# calefactor.net
KiCad netlist of a schematic drawn in EAGLE
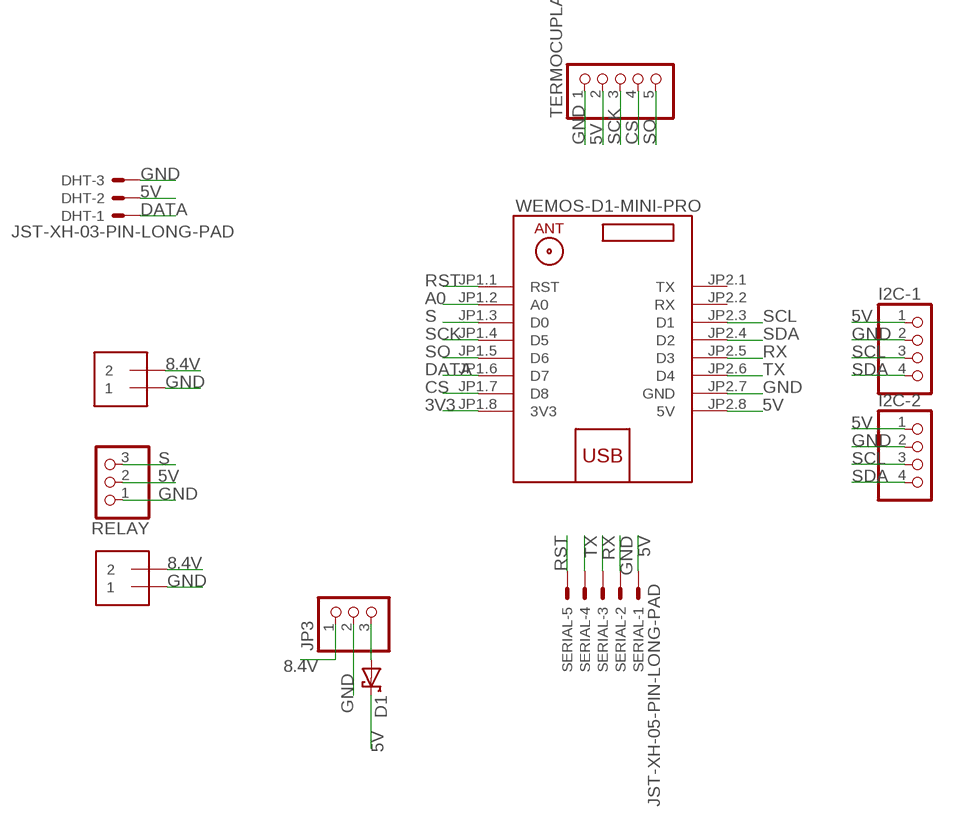
[diagram p0: schematic, sheet 1]

(export (version "E")
  (design (tool "Eeschema 10.0.6"))
  (components
    (comp (ref "D1")
      (value "SCHOTTKY-DIODEDO41-7")
      (footprint "eagle-import:DO41-7")
      (libsource (lib "eagle-import") (part "SCHOTTKY-DIODEDO41-7"))
    )
    (comp (ref "DHT")
      (value "JST-XH-03-PIN-LONG-PAD")
      (footprint "eagle-import:JST-XH-03-PACKAGE-LONG-PAD")
      (libsource (lib "eagle-import") (part "JST-XH-03-PIN-LONG-PAD"))
    )
    (comp (ref "I2C-1")
      (value "PINHD-1X4")
      (footprint "eagle-import:1X04")
      (libsource (lib "eagle-import") (part "PINHD-1X4"))
    )
    (comp (ref "I2C-2")
      (value "PINHD-1X4")
      (footprint "eagle-import:1X04")
      (libsource (lib "eagle-import") (part "PINHD-1X4"))
    )
    (comp (ref "J1")
      (value "1X2-3.5MM")
      (footprint "eagle-import:1X2-3.5MM")
      (libsource (lib "eagle-import") (part "1X2-3.5MM"))
    )
    (comp (ref "J2")
      (value "1X2-3.5MM")
      (footprint "eagle-import:1X2-3.5MM")
      (libsource (lib "eagle-import") (part "1X2-3.5MM"))
    )
    (comp (ref "JP3")
      (value "PINHD-1X3")
      (footprint "eagle-import:1X03")
      (libsource (lib "eagle-import") (part "PINHD-1X3"))
    )
    (comp (ref "RELAY")
      (value "PINHD-1X3")
      (footprint "eagle-import:1X03")
      (libsource (lib "eagle-import") (part "PINHD-1X3"))
    )
    (comp (ref "SERIAL")
      (value "JST-XH-05-PIN-LONG-PAD")
      (footprint "eagle-import:JST-XH-05-PACKAGE-LONG-PAD")
      (libsource (lib "eagle-import") (part "JST-XH-05-PIN-LONG-PAD"))
    )
    (comp (ref "TERMOCUPLA")
      (value "PINHD-1X5")
      (footprint "eagle-import:1X05")
      (libsource (lib "eagle-import") (part "PINHD-1X5"))
    )
    (comp (ref "U$1")
      (value "WEMOS-D1-MINI-PRO")
      (footprint "eagle-import:WEMOS-D1-MINI-PRO")
      (libsource (lib "eagle-import") (part "WEMOS-D1-MINI-PRO"))
    )
  )
  (nets
    (net (code "1") (name "/3V3") (class "Default")
      (node (ref "U$1") (pin "JP1.8") (pinfunction "3V3_JP1.8") (pintype "power_in"))
    )
    (net (code "2") (name "/5V") (class "Default")
      (node (ref "D1") (pin "C") (pinfunction "C_C") (pintype "passive"))
      (node (ref "DHT") (pin "2") (pinfunction "S_2") (pintype "passive"))
      (node (ref "I2C-1") (pin "1") (pinfunction "1_1") (pintype "passive"))
      (node (ref "I2C-2") (pin "1") (pinfunction "1_1") (pintype "passive"))
      (node (ref "RELAY") (pin "2") (pinfunction "2_2") (pintype "passive"))
      (node (ref "SERIAL") (pin "1") (pinfunction "S_1") (pintype "passive"))
      (node (ref "TERMOCUPLA") (pin "2") (pinfunction "2_2") (pintype "passive"))
      (node (ref "U$1") (pin "JP2.8") (pinfunction "5V_JP2.8") (pintype "power_in"))
    )
    (net (code "3") (name "/8.4V") (class "Default")
      (node (ref "J1") (pin "2") (pinfunction "2_2") (pintype "passive"))
      (node (ref "J2") (pin "2") (pinfunction "2_2") (pintype "passive"))
      (node (ref "JP3") (pin "1") (pinfunction "1_1") (pintype "passive"))
    )
    (net (code "4") (name "/A0") (class "Default")
      (node (ref "U$1") (pin "JP1.2") (pinfunction "A0_JP1.2") (pintype "bidirectional"))
    )
    (net (code "5") (name "/CS") (class "Default")
      (node (ref "TERMOCUPLA") (pin "4") (pinfunction "4_4") (pintype "passive"))
      (node (ref "U$1") (pin "JP1.7") (pinfunction "D8_JP1.7") (pintype "bidirectional"))
    )
    (net (code "6") (name "/DATA") (class "Default")
      (node (ref "DHT") (pin "1") (pinfunction "S_1") (pintype "passive"))
      (node (ref "U$1") (pin "JP1.6") (pinfunction "D7_JP1.6") (pintype "bidirectional"))
    )
    (net (code "7") (name "/GND") (class "Default")
      (node (ref "DHT") (pin "3") (pinfunction "S_3") (pintype "passive"))
      (node (ref "I2C-1") (pin "2") (pinfunction "2_2") (pintype "passive"))
      (node (ref "I2C-2") (pin "2") (pinfunction "2_2") (pintype "passive"))
      (node (ref "J1") (pin "1") (pinfunction "1_1") (pintype "passive"))
      (node (ref "J2") (pin "1") (pinfunction "1_1") (pintype "passive"))
      (node (ref "JP3") (pin "2") (pinfunction "2_2") (pintype "passive"))
      (node (ref "RELAY") (pin "1") (pinfunction "1_1") (pintype "passive"))
      (node (ref "SERIAL") (pin "2") (pinfunction "S_2") (pintype "passive"))
      (node (ref "TERMOCUPLA") (pin "1") (pinfunction "1_1") (pintype "passive"))
      (node (ref "U$1") (pin "JP2.7") (pinfunction "GND_JP2.7") (pintype "power_in"))
    )
    (net (code "8") (name "/RST") (class "Default")
      (node (ref "SERIAL") (pin "5") (pinfunction "S_5") (pintype "passive"))
      (node (ref "U$1") (pin "JP1.1") (pinfunction "RST_JP1.1") (pintype "bidirectional"))
    )
    (net (code "9") (name "/RX") (class "Default")
      (node (ref "SERIAL") (pin "3") (pinfunction "S_3") (pintype "passive"))
      (node (ref "U$1") (pin "JP2.5") (pinfunction "D3_JP2.5") (pintype "bidirectional"))
    )
    (net (code "10") (name "/S") (class "Default")
      (node (ref "RELAY") (pin "3") (pinfunction "3_3") (pintype "passive"))
      (node (ref "U$1") (pin "JP1.3") (pinfunction "D0_JP1.3") (pintype "bidirectional"))
    )
    (net (code "11") (name "/SCK") (class "Default")
      (node (ref "TERMOCUPLA") (pin "3") (pinfunction "3_3") (pintype "passive"))
      (node (ref "U$1") (pin "JP1.4") (pinfunction "D5_JP1.4") (pintype "bidirectional"))
    )
    (net (code "12") (name "/SCL") (class "Default")
      (node (ref "I2C-1") (pin "3") (pinfunction "3_3") (pintype "passive"))
      (node (ref "I2C-2") (pin "3") (pinfunction "3_3") (pintype "passive"))
      (node (ref "U$1") (pin "JP2.3") (pinfunction "D1_JP2.3") (pintype "bidirectional"))
    )
    (net (code "13") (name "/SDA") (class "Default")
      (node (ref "I2C-1") (pin "4") (pinfunction "4_4") (pintype "passive"))
      (node (ref "I2C-2") (pin "4") (pinfunction "4_4") (pintype "passive"))
      (node (ref "U$1") (pin "JP2.4") (pinfunction "D2_JP2.4") (pintype "bidirectional"))
    )
    (net (code "14") (name "/SO") (class "Default")
      (node (ref "TERMOCUPLA") (pin "5") (pinfunction "5_5") (pintype "passive"))
      (node (ref "U$1") (pin "JP1.5") (pinfunction "D6_JP1.5") (pintype "bidirectional"))
    )
    (net (code "15") (name "/TX") (class "Default")
      (node (ref "SERIAL") (pin "4") (pinfunction "S_4") (pintype "passive"))
      (node (ref "U$1") (pin "JP2.6") (pinfunction "D4_JP2.6") (pintype "bidirectional"))
    )
    (net (code "16") (name "Net-(D1-PadA)") (class "Default")
      (node (ref "D1") (pin "A") (pinfunction "A_A") (pintype "passive"))
      (node (ref "JP3") (pin "3") (pinfunction "3_3") (pintype "passive"))
    )
    (net (code "17") (name "unconnected-(U$1-RX-PadJP2.2)") (class "Default")
      (node (ref "U$1") (pin "JP2.2") (pinfunction "RX_JP2.2") (pintype "bidirectional"))
    )
    (net (code "18") (name "unconnected-(U$1-TX-PadJP2.1)") (class "Default")
      (node (ref "U$1") (pin "JP2.1") (pinfunction "TX_JP2.1") (pintype "bidirectional"))
    )
  )
)
